# CAN_Steering_Wheel.net
KiCad netlist of a schematic drawn in EAGLE
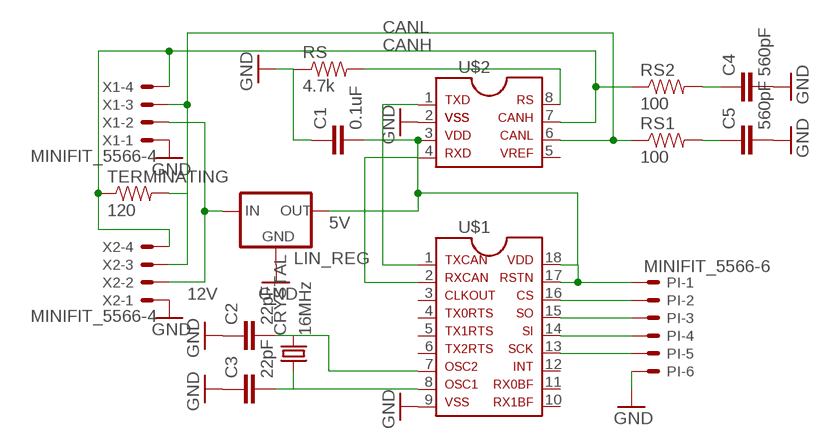
[diagram p0: schematic, sheet 1]

(export (version "E")
  (design (tool "Eeschema 10.0.6"))
  (components
    (comp (ref "C1")
      (value "0.1uF")
      (footprint "eagle-import:0805")
      (libsource (lib "eagle-import") (part "CAP0805"))
    )
    (comp (ref "C2")
      (value "22pF")
      (footprint "eagle-import:0805")
      (libsource (lib "eagle-import") (part "CAP0805"))
    )
    (comp (ref "C3")
      (value "22pF")
      (footprint "eagle-import:0805")
      (libsource (lib "eagle-import") (part "CAP0805"))
    )
    (comp (ref "C4")
      (value "560pF")
      (footprint "eagle-import:0805")
      (libsource (lib "eagle-import") (part "CAP0805"))
    )
    (comp (ref "C5")
      (value "560pF")
      (footprint "eagle-import:0805")
      (libsource (lib "eagle-import") (part "CAP0805"))
    )
    (comp (ref "CRYSTAL")
      (value "16MHz")
      (footprint "eagle-import:HC49UP")
      (libsource (lib "eagle-import") (part "CRYSTALSMD"))
    )
    (comp (ref "LIN_REG")
      (value "5V_REGULATOR_LM340-NLM340MPX-5.0/NOPB")
      (footprint "eagle-import:SOT223")
      (libsource (lib "eagle-import") (part "5V_REGULATOR_LM340-NLM340MPX-5.0/NOPB"))
    )
    (comp (ref "PI")
      (value "MINIFIT_5566-6")
      (footprint "eagle-import:MINIFIT_5566-6")
      (fields (field (name "MPN") "95566-61002"))
      (libsource (lib "eagle-import") (part "MINIFIT_5566-6"))
    )
    (comp (ref "RS")
      (value "4.7k")
      (footprint "eagle-import:0805")
      (libsource (lib "eagle-import") (part "RESISTOR0805-RES"))
    )
    (comp (ref "RS1")
      (value "100")
      (footprint "eagle-import:0805")
      (libsource (lib "eagle-import") (part "RESISTOR0805-RES"))
    )
    (comp (ref "RS2")
      (value "100")
      (footprint "eagle-import:0805")
      (libsource (lib "eagle-import") (part "RESISTOR0805-RES"))
    )
    (comp (ref "TERMINATING")
      (value "120")
      (footprint "eagle-import:0805")
      (libsource (lib "eagle-import") (part "RESISTOR0805-RES"))
    )
    (comp (ref "U$1")
      (value "MCP2515SMD")
      (footprint "eagle-import:SOIC-18W")
      (libsource (lib "eagle-import") (part "MCP2515SMD"))
    )
    (comp (ref "U$2")
      (value "MCP2551")
      (footprint "eagle-import:SOIC-08")
      (libsource (lib "eagle-import") (part "MCP2551"))
    )
    (comp (ref "X1")
      (value "MINIFIT_5566-4")
      (footprint "eagle-import:MINIFIT_5566-4")
      (libsource (lib "eagle-import") (part "MINIFIT_5566-4"))
    )
    (comp (ref "X2")
      (value "MINIFIT_5566-4")
      (footprint "eagle-import:MINIFIT_5566-4")
      (libsource (lib "eagle-import") (part "MINIFIT_5566-4"))
    )
  )
  (nets
    (net (code "1") (name "/5V") (class "Default")
      (node (ref "C1") (pin "2") (pinfunction "2_2") (pintype "passive"))
      (node (ref "LIN_REG") (pin "3") (pinfunction "OUT_3") (pintype "output"))
      (node (ref "PI") (pin "1") (pinfunction "S_1") (pintype "passive"))
      (node (ref "U$1") (pin "17") (pinfunction "17_17") (pintype "passive"))
      (node (ref "U$1") (pin "18") (pinfunction "18_18") (pintype "passive"))
      (node (ref "U$2") (pin "3") (pinfunction "3_3") (pintype "passive"))
    )
    (net (code "2") (name "/12V") (class "Default")
      (node (ref "LIN_REG") (pin "1") (pinfunction "IN_1") (pintype "input"))
      (node (ref "X1") (pin "2") (pinfunction "S_2") (pintype "passive"))
      (node (ref "X2") (pin "2") (pinfunction "S_2") (pintype "passive"))
    )
    (net (code "3") (name "/CANH") (class "Default")
      (node (ref "RS2") (pin "1") (pinfunction "1_1") (pintype "passive"))
      (node (ref "TERMINATING") (pin "1") (pinfunction "1_1") (pintype "passive"))
      (node (ref "U$2") (pin "7") (pinfunction "7_7") (pintype "passive"))
      (node (ref "X1") (pin "4") (pinfunction "S_4") (pintype "passive"))
      (node (ref "X2") (pin "4") (pinfunction "S_4") (pintype "passive"))
    )
    (net (code "4") (name "/CANL") (class "Default")
      (node (ref "RS1") (pin "1") (pinfunction "1_1") (pintype "passive"))
      (node (ref "TERMINATING") (pin "2") (pinfunction "2_2") (pintype "passive"))
      (node (ref "U$2") (pin "6") (pinfunction "6_6") (pintype "passive"))
      (node (ref "X1") (pin "3") (pinfunction "S_3") (pintype "passive"))
      (node (ref "X2") (pin "3") (pinfunction "S_3") (pintype "passive"))
    )
    (net (code "5") (name "GND") (class "Default")
      (node (ref "C1") (pin "1") (pinfunction "1_1") (pintype "passive"))
      (node (ref "C2") (pin "1") (pinfunction "1_1") (pintype "passive"))
      (node (ref "C3") (pin "1") (pinfunction "1_1") (pintype "passive"))
      (node (ref "C4") (pin "2") (pinfunction "2_2") (pintype "passive"))
      (node (ref "C5") (pin "2") (pinfunction "2_2") (pintype "passive"))
      (node (ref "LIN_REG") (pin "2") (pinfunction "GND_2") (pintype "input"))
      (node (ref "LIN_REG") (pin "4") (pinfunction "GND_4") (pintype "input"))
      (node (ref "PI") (pin "6") (pinfunction "S_6") (pintype "passive"))
      (node (ref "RS") (pin "1") (pinfunction "1_1") (pintype "passive"))
      (node (ref "U$1") (pin "9") (pinfunction "9_9") (pintype "passive"))
      (node (ref "U$2") (pin "2") (pinfunction "2_2") (pintype "passive"))
      (node (ref "X1") (pin "1") (pinfunction "S_1") (pintype "passive"))
      (node (ref "X2") (pin "1") (pinfunction "S_1") (pintype "passive"))
    )
    (net (code "6") (name "Net-(C2-Pad2)") (class "Default")
      (node (ref "C2") (pin "2") (pinfunction "2_2") (pintype "passive"))
      (node (ref "CRYSTAL") (pin "2") (pinfunction "2_2") (pintype "passive"))
      (node (ref "U$1") (pin "7") (pinfunction "7_7") (pintype "passive"))
    )
    (net (code "7") (name "Net-(C3-Pad2)") (class "Default")
      (node (ref "C3") (pin "2") (pinfunction "2_2") (pintype "passive"))
      (node (ref "CRYSTAL") (pin "1") (pinfunction "1_1") (pintype "passive"))
      (node (ref "U$1") (pin "8") (pinfunction "8_8") (pintype "passive"))
    )
    (net (code "8") (name "Net-(C4-Pad1)") (class "Default")
      (node (ref "C4") (pin "1") (pinfunction "1_1") (pintype "passive"))
      (node (ref "RS2") (pin "2") (pinfunction "2_2") (pintype "passive"))
    )
    (net (code "9") (name "Net-(C5-Pad1)") (class "Default")
      (node (ref "C5") (pin "1") (pinfunction "1_1") (pintype "passive"))
      (node (ref "RS1") (pin "2") (pinfunction "2_2") (pintype "passive"))
    )
    (net (code "10") (name "Net-(PIB-S)") (class "Default")
      (node (ref "PI") (pin "2") (pinfunction "S_2") (pintype "passive"))
      (node (ref "U$1") (pin "16") (pinfunction "16_16") (pintype "passive"))
    )
    (net (code "11") (name "Net-(PIC-S)") (class "Default")
      (node (ref "PI") (pin "3") (pinfunction "S_3") (pintype "passive"))
      (node (ref "U$1") (pin "15") (pinfunction "15_15") (pintype "passive"))
    )
    (net (code "12") (name "Net-(PID-S)") (class "Default")
      (node (ref "PI") (pin "4") (pinfunction "S_4") (pintype "passive"))
      (node (ref "U$1") (pin "14") (pinfunction "14_14") (pintype "passive"))
    )
    (net (code "13") (name "Net-(PIE-S)") (class "Default")
      (node (ref "PI") (pin "5") (pinfunction "S_5") (pintype "passive"))
      (node (ref "U$1") (pin "13") (pinfunction "13_13") (pintype "passive"))
    )
    (net (code "14") (name "Net-(RS-Pad2)") (class "Default")
      (node (ref "RS") (pin "2") (pinfunction "2_2") (pintype "passive"))
      (node (ref "U$2") (pin "8") (pinfunction "8_8") (pintype "passive"))
    )
    (net (code "15") (name "Net-(U$1-Pad1)") (class "Default")
      (node (ref "U$1") (pin "1") (pinfunction "1_1") (pintype "passive"))
      (node (ref "U$2") (pin "1") (pinfunction "1_1") (pintype "passive"))
    )
    (net (code "16") (name "Net-(U$1-Pad2)") (class "Default")
      (node (ref "U$1") (pin "2") (pinfunction "2_2") (pintype "passive"))
      (node (ref "U$2") (pin "4") (pinfunction "4_4") (pintype "passive"))
    )
    (net (code "17") (name "unconnected-(U$1-Pad3)") (class "Default")
      (node (ref "U$1") (pin "3") (pinfunction "3_3") (pintype "passive"))
    )
    (net (code "18") (name "unconnected-(U$1-Pad4)") (class "Default")
      (node (ref "U$1") (pin "4") (pinfunction "4_4") (pintype "passive"))
    )
    (net (code "19") (name "unconnected-(U$1-Pad5)") (class "Default")
      (node (ref "U$1") (pin "5") (pinfunction "5_5") (pintype "passive"))
    )
    (net (code "20") (name "unconnected-(U$1-Pad6)") (class "Default")
      (node (ref "U$1") (pin "6") (pinfunction "6_6") (pintype "passive"))
    )
    (net (code "21") (name "unconnected-(U$1-Pad10)") (class "Default")
      (node (ref "U$1") (pin "10") (pinfunction "10_10") (pintype "passive"))
    )
    (net (code "22") (name "unconnected-(U$1-Pad11)") (class "Default")
      (node (ref "U$1") (pin "11") (pinfunction "11_11") (pintype "passive"))
    )
    (net (code "23") (name "unconnected-(U$1-Pad12)") (class "Default")
      (node (ref "U$1") (pin "12") (pinfunction "12_12") (pintype "passive"))
    )
    (net (code "24") (name "unconnected-(U$2-Pad5)") (class "Default")
      (node (ref "U$2") (pin "5") (pinfunction "5_5") (pintype "passive"))
    )
  )
)
